# Spgsregler.net
KiCad netlist of a schematic drawn in EAGLE
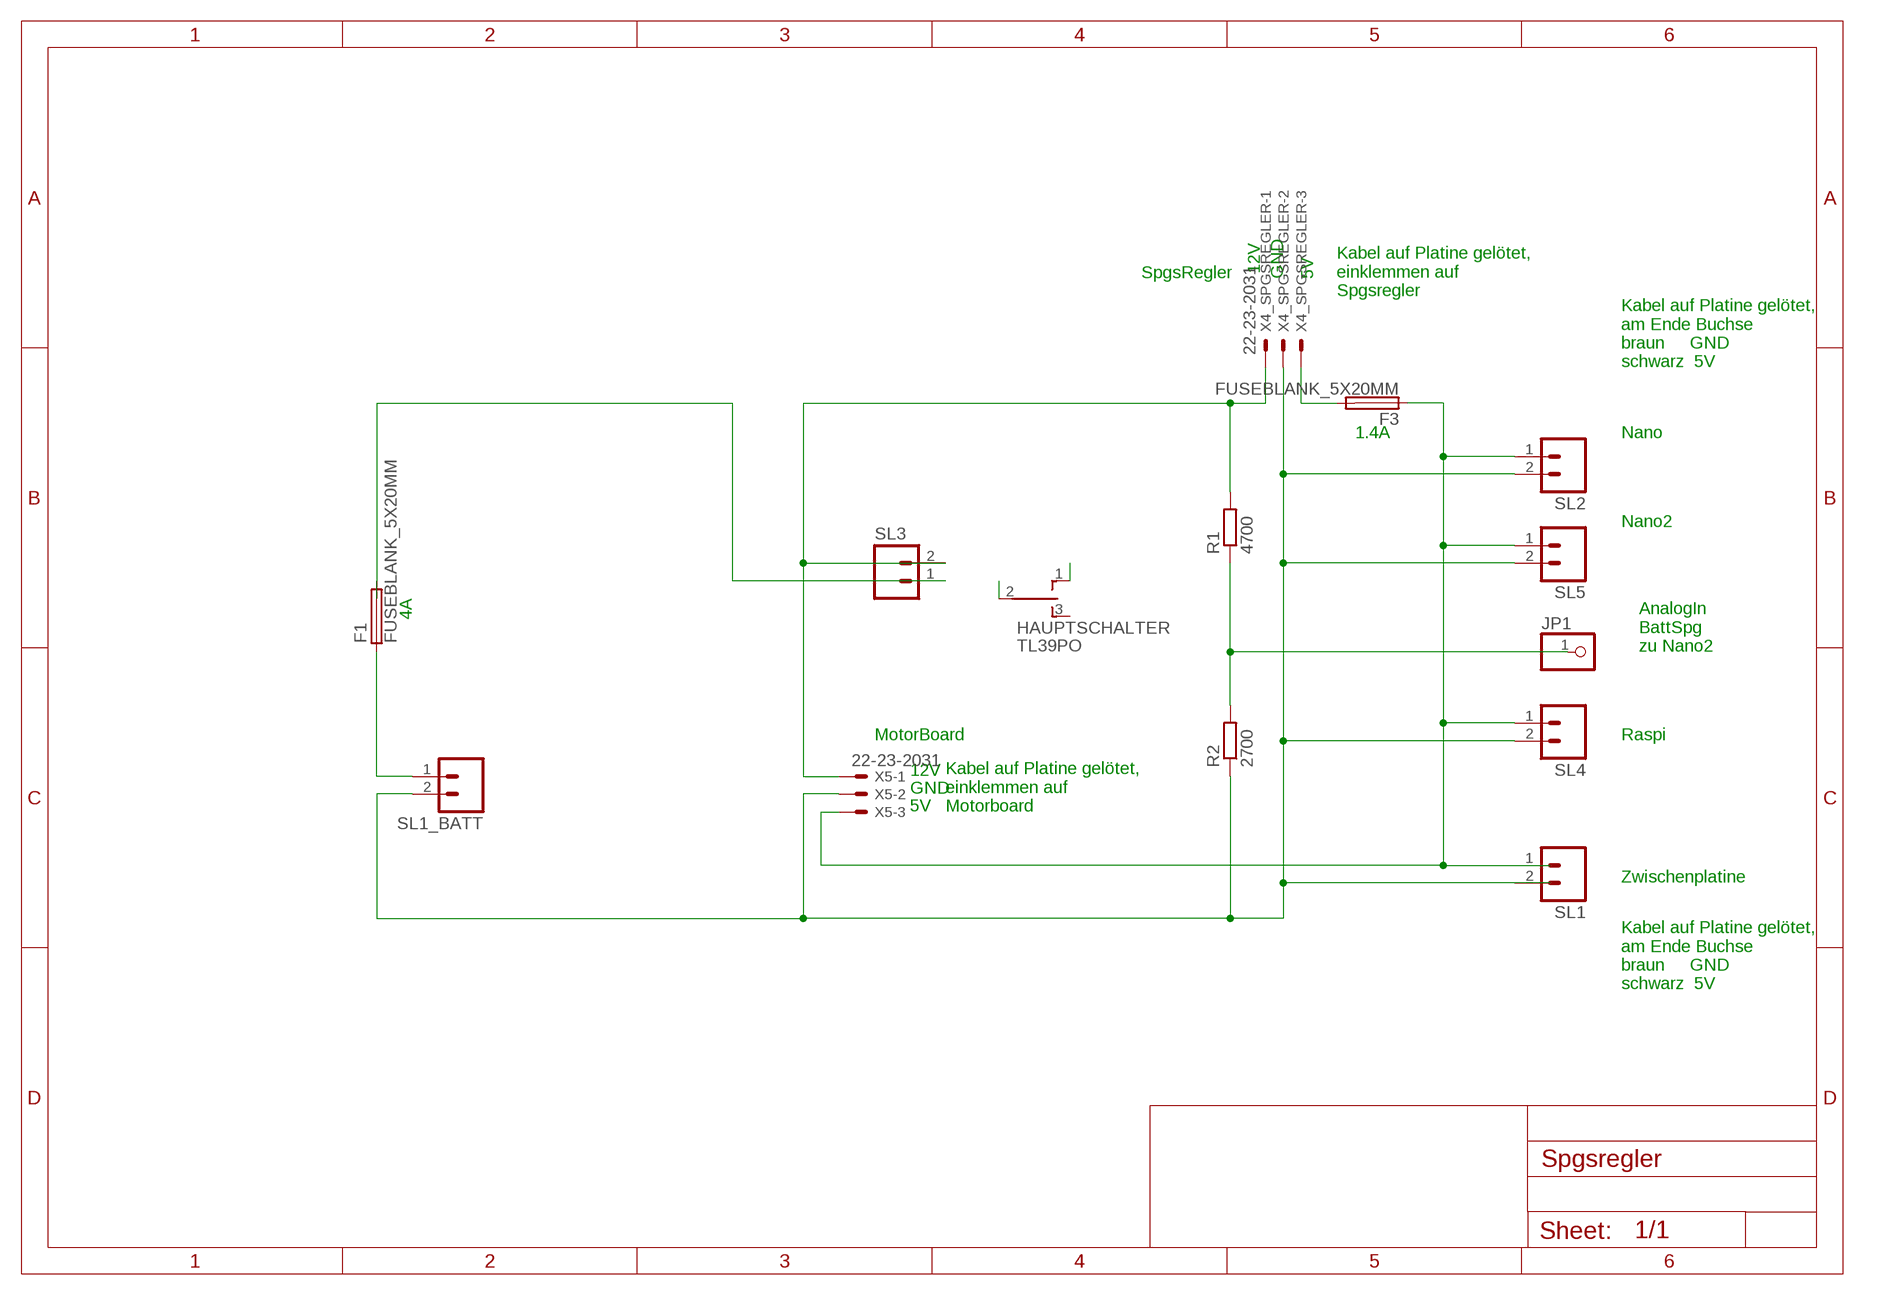
[diagram p0: schematic, sheet 1]

(export (version "E")
  (design (tool "Eeschema 10.0.6"))
  (components
    (comp (ref "F1")
      (value "FUSEBLANK_5X20MM")
      (footprint "eagle-import:FUSE_HOLDER_5X20MM")
      (libsource (lib "eagle-import") (part "FUSEBLANK_5X20MM"))
    )
    (comp (ref "F3")
      (value "FUSEBLANK_5X20MM")
      (footprint "eagle-import:FUSE_HOLDER_5X20MM")
      (libsource (lib "eagle-import") (part "FUSEBLANK_5X20MM"))
    )
    (comp (ref "HAUPTSCHALTER")
      (value "TL39PO")
      (footprint "eagle-import:TL3XPO")
      (libsource (lib "eagle-import") (part "TL39PO"))
    )
    (comp (ref "JP1")
      (value "PINHD-1X1")
      (footprint "eagle-import:1X01")
      (libsource (lib "eagle-import") (part "PINHD-1X1"))
    )
    (comp (ref "R1")
      (value "4700")
      (footprint "eagle-import:0207_10")
      (libsource (lib "eagle-import") (part "R-EU_0207/10"))
    )
    (comp (ref "R2")
      (value "2700")
      (footprint "eagle-import:0207_10")
      (libsource (lib "eagle-import") (part "R-EU_0207/10"))
    )
    (comp (ref "SL1")
      (value "M02")
      (footprint "eagle-import:02P")
      (libsource (lib "eagle-import") (part "M02"))
    )
    (comp (ref "SL1_BATT")
      (value "M02")
      (footprint "eagle-import:02P")
      (libsource (lib "eagle-import") (part "M02"))
    )
    (comp (ref "SL2")
      (value "M02")
      (footprint "eagle-import:02P")
      (libsource (lib "eagle-import") (part "M02"))
    )
    (comp (ref "SL3")
      (value "M02")
      (footprint "eagle-import:02P")
      (libsource (lib "eagle-import") (part "M02"))
    )
    (comp (ref "SL4")
      (value "M02")
      (footprint "eagle-import:02P")
      (libsource (lib "eagle-import") (part "M02"))
    )
    (comp (ref "SL5")
      (value "M02")
      (footprint "eagle-import:02P")
      (libsource (lib "eagle-import") (part "M02"))
    )
    (comp (ref "X4_SPGSREGLER")
      (value "22-23-2031")
      (footprint "eagle-import:22-23-2031")
      (fields (field (name "MF") "MOLEX"))
      (libsource (lib "eagle-import") (part "22-23-2031"))
    )
    (comp (ref "X5")
      (value "22-23-2031")
      (footprint "eagle-import:22-23-2031")
      (fields (field (name "MF") "MOLEX"))
      (libsource (lib "eagle-import") (part "22-23-2031"))
    )
  )
  (nets
    (net (code "1") (name "Net-(F1-Pad1)") (class "Default")
      (node (ref "F1") (pin "1") (pinfunction "1_1") (pintype "passive"))
      (node (ref "SL1_BATT") (pin "1") (pinfunction "1_1") (pintype "passive"))
    )
    (net (code "2") (name "Net-(F1-Pad2)") (class "Default")
      (node (ref "F1") (pin "2") (pinfunction "2_2") (pintype "passive"))
      (node (ref "SL3") (pin "1") (pinfunction "1_1") (pintype "passive"))
    )
    (net (code "3") (name "Net-(JP1-Pad1)") (class "Default")
      (node (ref "JP1") (pin "1") (pinfunction "1_1") (pintype "passive"))
      (node (ref "R1") (pin "1") (pinfunction "1_1") (pintype "passive"))
      (node (ref "R2") (pin "2") (pinfunction "2_2") (pintype "passive"))
    )
    (net (code "4") (name "Net-(X4_SPGSREGLERA-S)") (class "Default")
      (node (ref "R1") (pin "2") (pinfunction "2_2") (pintype "passive"))
      (node (ref "SL3") (pin "2") (pinfunction "2_2") (pintype "passive"))
      (node (ref "X4_SPGSREGLER") (pin "1") (pinfunction "S_1") (pintype "passive"))
      (node (ref "X5") (pin "1") (pinfunction "S_1") (pintype "passive"))
    )
    (net (code "5") (name "Net-(X4_SPGSREGLERB-S)") (class "Default")
      (node (ref "R2") (pin "1") (pinfunction "1_1") (pintype "passive"))
      (node (ref "SL1_BATT") (pin "2") (pinfunction "2_2") (pintype "passive"))
      (node (ref "SL2") (pin "2") (pinfunction "2_2") (pintype "passive"))
      (node (ref "SL4") (pin "2") (pinfunction "2_2") (pintype "passive"))
      (node (ref "SL5") (pin "2") (pinfunction "2_2") (pintype "passive"))
      (node (ref "X4_SPGSREGLER") (pin "2") (pinfunction "S_2") (pintype "passive"))
      (node (ref "X5") (pin "2") (pinfunction "S_2") (pintype "passive"))
    )
    (net (code "6") (name "Net-(X4_SPGSREGLERC-S)") (class "Default")
      (node (ref "F3") (pin "2") (pinfunction "2_2") (pintype "passive"))
      (node (ref "X4_SPGSREGLER") (pin "3") (pinfunction "S_3") (pintype "passive"))
    )
    (net (code "7") (name "Net-(X5C-S)") (class "Default")
      (node (ref "F3") (pin "1") (pinfunction "1_1") (pintype "passive"))
      (node (ref "SL2") (pin "1") (pinfunction "1_1") (pintype "passive"))
      (node (ref "SL4") (pin "1") (pinfunction "1_1") (pintype "passive"))
      (node (ref "SL5") (pin "1") (pinfunction "1_1") (pintype "passive"))
      (node (ref "X5") (pin "3") (pinfunction "S_3") (pintype "passive"))
    )
    (net (code "8") (name "unconnected-(HAUPTSCHALTER-O-Pad1)") (class "Default")
      (node (ref "HAUPTSCHALTER") (pin "1") (pinfunction "O_1") (pintype "passive"))
    )
    (net (code "9") (name "unconnected-(HAUPTSCHALTER-P-Pad2)") (class "Default")
      (node (ref "HAUPTSCHALTER") (pin "2") (pinfunction "P_2") (pintype "passive"))
    )
    (net (code "10") (name "unconnected-(HAUPTSCHALTER-S-Pad3)") (class "Default")
      (node (ref "HAUPTSCHALTER") (pin "3") (pinfunction "S_3") (pintype "passive"))
    )
    (net (code "11") (name "unconnected-(SL1-Pad1)") (class "Default")
      (node (ref "SL1") (pin "1") (pinfunction "1_1") (pintype "passive"))
    )
    (net (code "12") (name "unconnected-(SL1-Pad2)") (class "Default")
      (node (ref "SL1") (pin "2") (pinfunction "2_2") (pintype "passive"))
    )
  )
)
